# HSD_Enable_Iso.net
KiCad netlist of a schematic drawn in Altium Designer
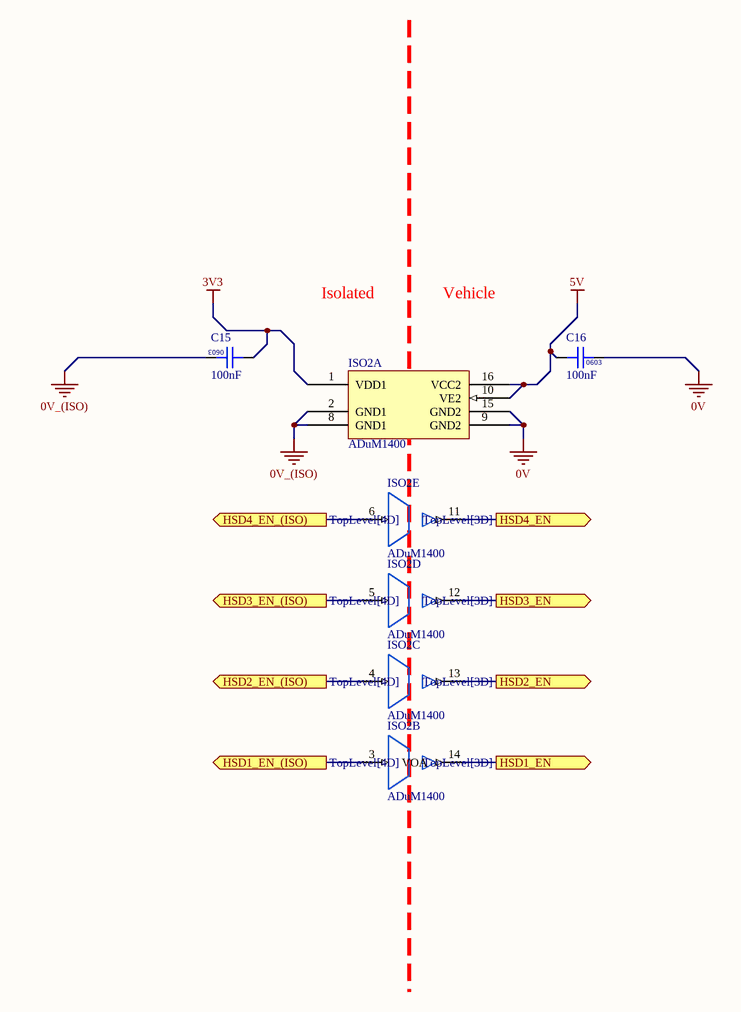
[diagram p0: HSD Enable Iso.SchDoc]

(export (version "E")
  (design (tool "Eeschema 10.0.6"))
  (components
    (comp (ref "C15")
      (value "100nF")
      (footprint "0603")
      (fields
        (field (name "PART NUMBER") "GCM188L81H104KA57D")
        (field (name "MANUFACTURER") "muRata")
        (field (name "TOLERANCE") "±10%")
      )
      (libsource (lib "ts_standard_library") (part "Capacitor 0603"))
    )
    (comp (ref "C16")
      (value "100nF")
      (footprint "0603")
      (fields
        (field (name "PART NUMBER") "GCM188L81H104KA57D")
        (field (name "MANUFACTURER") "muRata")
        (field (name "TOLERANCE") "±10%")
      )
      (libsource (lib "ts_standard_library") (part "Capacitor 0603"))
    )
    (comp (ref "ISO2")
      (value "ADuM1400")
      (footprint "AD 16-SOIC")
      (fields
        (field (name "MANUFACTURER") "Analog Devices")
        (field (name "DIGIKEY PART NUMBER") "ADUM1400WSRWZ-ND")
      )
      (libsource (lib "ts_standard_library") (part "ADuM1400"))
    )
  )
  (nets
    (net (code "1") (name "/HSD1_EN") (class "Default")
      (node (ref "ISO2") (pin "14") (pinfunction "VOA_14") (pintype "output"))
    )
    (net (code "2") (name "/HSD1_EN_(ISO)") (class "Default")
      (node (ref "ISO2") (pin "3") (pinfunction "VIA_3") (pintype "input"))
    )
    (net (code "3") (name "/HSD2_EN") (class "Default")
      (node (ref "ISO2") (pin "13") (pinfunction "VOB_13") (pintype "output"))
    )
    (net (code "4") (name "/HSD2_EN_(ISO)") (class "Default")
      (node (ref "ISO2") (pin "4") (pinfunction "VIB_4") (pintype "input"))
    )
    (net (code "5") (name "/HSD3_EN") (class "Default")
      (node (ref "ISO2") (pin "12") (pinfunction "VOC_12") (pintype "output"))
    )
    (net (code "6") (name "/HSD3_EN_(ISO)") (class "Default")
      (node (ref "ISO2") (pin "5") (pinfunction "VIC_5") (pintype "input"))
    )
    (net (code "7") (name "/HSD4_EN") (class "Default")
      (node (ref "ISO2") (pin "11") (pinfunction "VOD_11") (pintype "output"))
    )
    (net (code "8") (name "/HSD4_EN_(ISO)") (class "Default")
      (node (ref "ISO2") (pin "6") (pinfunction "VID_6") (pintype "input"))
    )
    (net (code "9") (name "0V") (class "Default")
      (node (ref "C16") (pin "2") (pinfunction "2_2") (pintype "passive"))
      (node (ref "ISO2") (pin "15") (pinfunction "GND2_15") (pintype "power_in"))
      (node (ref "ISO2") (pin "9") (pinfunction "GND2_9") (pintype "power_in"))
    )
    (net (code "10") (name "0V_(ISO)") (class "Default")
      (node (ref "C15") (pin "2") (pinfunction "2_2") (pintype "passive"))
      (node (ref "ISO2") (pin "2") (pinfunction "GND1_2") (pintype "power_in"))
      (node (ref "ISO2") (pin "8") (pinfunction "GND1_8") (pintype "power_in"))
    )
    (net (code "11") (name "3V3") (class "Default")
      (node (ref "C15") (pin "1") (pinfunction "1_1") (pintype "passive"))
      (node (ref "ISO2") (pin "1") (pinfunction "VDD1_1") (pintype "power_in"))
    )
    (net (code "12") (name "5V") (class "Default")
      (node (ref "C16") (pin "1") (pinfunction "1_1") (pintype "passive"))
      (node (ref "ISO2") (pin "10") (pinfunction "VE2_10") (pintype "input"))
      (node (ref "ISO2") (pin "16") (pinfunction "VCC2_16") (pintype "power_in"))
    )
  )
)
